# chariot_comms_b.net
KiCad netlist of a schematic drawn in EAGLE
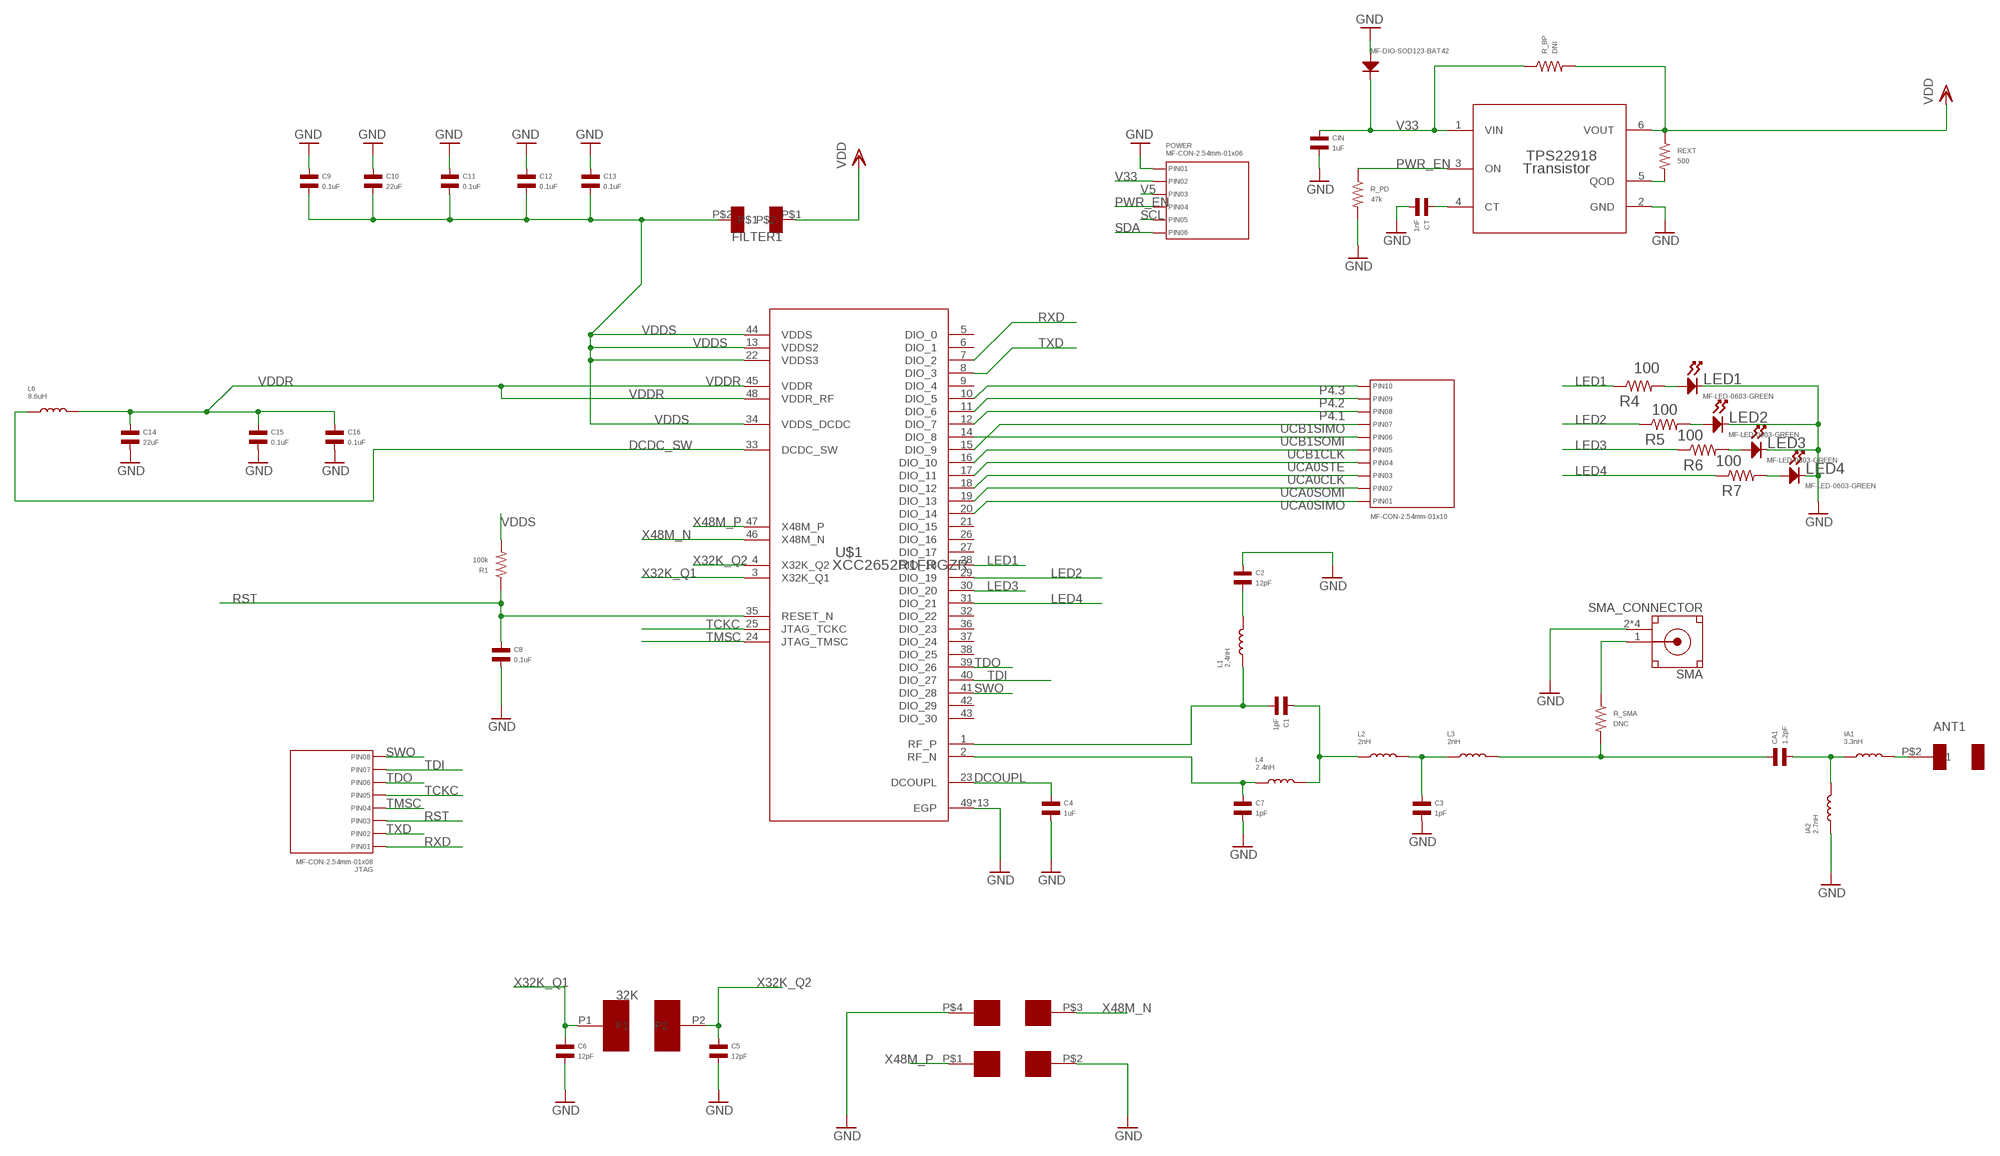
[diagram p0: schematic, sheet 1]

(export (version "E")
  (design (tool "Eeschema 10.0.6"))
  (components
    (comp (ref "32K")
      (value "FC-135")
      (footprint "eagle-import:FC-135")
      (libsource (lib "eagle-import") (part "FC-135"))
    )
    (comp (ref "48M")
      (value "NX2016SA-48M-EXS00A-CS05517")
      (footprint "eagle-import:NX2016SA-48M-EXS00A-CS05517")
      (libsource (lib "eagle-import") (part "NX2016SA-48M-EXS00A-CS05517"))
    )
    (comp (ref "ANT1")
      (value "2450AT18B100E")
      (footprint "eagle-import:2450AT18B100E")
      (libsource (lib "eagle-import") (part "2450AT18B100E"))
    )
    (comp (ref "C1")
      (value "1pF")
      (footprint "eagle-import:C0603")
      (libsource (lib "eagle-import") (part "CAPACITOR_NP_0603"))
    )
    (comp (ref "C2")
      (value "12pF")
      (footprint "eagle-import:C0603")
      (libsource (lib "eagle-import") (part "CAPACITOR_NP_0603"))
    )
    (comp (ref "C3")
      (value "1pF")
      (footprint "eagle-import:C0603")
      (libsource (lib "eagle-import") (part "CAPACITOR_NP_0603"))
    )
    (comp (ref "C4")
      (value "1uF")
      (footprint "eagle-import:C0603")
      (libsource (lib "eagle-import") (part "CAPACITOR_NP_0603"))
    )
    (comp (ref "C5")
      (value "12pF")
      (footprint "eagle-import:C0603")
      (libsource (lib "eagle-import") (part "CAPACITOR_NP_0603"))
    )
    (comp (ref "C6")
      (value "12pF")
      (footprint "eagle-import:C0603")
      (libsource (lib "eagle-import") (part "CAPACITOR_NP_0603"))
    )
    (comp (ref "C7")
      (value "1pF")
      (footprint "eagle-import:C0603")
      (libsource (lib "eagle-import") (part "CAPACITOR_NP_0603"))
    )
    (comp (ref "C8")
      (value "0.1uF")
      (footprint "eagle-import:C0603")
      (libsource (lib "eagle-import") (part "CAPACITOR_NP_0603"))
    )
    (comp (ref "C9")
      (value "0.1uF")
      (footprint "eagle-import:C0603")
      (libsource (lib "eagle-import") (part "CAPACITOR_NP_0603"))
    )
    (comp (ref "C10")
      (value "22uF")
      (footprint "eagle-import:C0603")
      (libsource (lib "eagle-import") (part "CAPACITOR_NP_0603"))
    )
    (comp (ref "C11")
      (value "0.1uF")
      (footprint "eagle-import:C0603")
      (libsource (lib "eagle-import") (part "CAPACITOR_NP_0603"))
    )
    (comp (ref "C12")
      (value "0.1uF")
      (footprint "eagle-import:C0603")
      (libsource (lib "eagle-import") (part "CAPACITOR_NP_0603"))
    )
    (comp (ref "C13")
      (value "0.1uF")
      (footprint "eagle-import:C0603")
      (libsource (lib "eagle-import") (part "CAPACITOR_NP_0603"))
    )
    (comp (ref "C14")
      (value "22uF")
      (footprint "eagle-import:C0603")
      (libsource (lib "eagle-import") (part "CAPACITOR_NP_0603"))
    )
    (comp (ref "C15")
      (value "0.1uF")
      (footprint "eagle-import:C0603")
      (libsource (lib "eagle-import") (part "CAPACITOR_NP_0603"))
    )
    (comp (ref "C16")
      (value "0.1uF")
      (footprint "eagle-import:C0603")
      (libsource (lib "eagle-import") (part "CAPACITOR_NP_0603"))
    )
    (comp (ref "CA1")
      (value "1.2pF")
      (footprint "eagle-import:C0603")
      (libsource (lib "eagle-import") (part "CAPACITOR_NP_0603"))
    )
    (comp (ref "CIN")
      (value "1uF")
      (footprint "eagle-import:C0603")
      (libsource (lib "eagle-import") (part "CAPACITOR_NP_0603"))
    )
    (comp (ref "COMMS_J")
      (value "MF-CON-2.54mm-01x10")
      (footprint "eagle-import:PTH_2.54MM_01X10")
      (fields (field (name "HOUSEPART") "YES"))
      (libsource (lib "eagle-import") (part "CON_01X10_PTH_2.54MM"))
    )
    (comp (ref "CT")
      (value "1nF")
      (footprint "eagle-import:C0603")
      (libsource (lib "eagle-import") (part "CAPACITOR_NP_0603"))
    )
    (comp (ref "D1")
      (value "MF-DIO-SOD123-BAT42")
      (footprint "eagle-import:SOD-123")
      (fields (field (name "HOUSEPART") "YES"))
      (libsource (lib "eagle-import") (part "DIODES_SOD-123_BAT42"))
    )
    (comp (ref "FILTER1")
      (value "BLM18HE152SN1D")
      (footprint "eagle-import:BLM18HE152SN1D")
      (libsource (lib "eagle-import") (part "BLM18HE152SN1D"))
    )
    (comp (ref "IA1")
      (value "3.3nH")
      (footprint "eagle-import:L0603")
      (libsource (lib "eagle-import") (part "INDUCTOR_0603"))
    )
    (comp (ref "IA2")
      (value "2.7nH")
      (footprint "eagle-import:L0603")
      (libsource (lib "eagle-import") (part "INDUCTOR_0603"))
    )
    (comp (ref "JTAG")
      (value "MF-CON-2.54mm-01x08")
      (footprint "eagle-import:PTH_2.54MM_01X08")
      (fields (field (name "HOUSEPART") "YES"))
      (libsource (lib "eagle-import") (part "CON_01X08_PTH_2.54MM"))
    )
    (comp (ref "L1")
      (value "2.4nH")
      (footprint "eagle-import:L0603")
      (libsource (lib "eagle-import") (part "INDUCTOR_0603"))
    )
    (comp (ref "L2")
      (value "2nH")
      (footprint "eagle-import:L0603")
      (libsource (lib "eagle-import") (part "INDUCTOR_0603"))
    )
    (comp (ref "L3")
      (value "2nH")
      (footprint "eagle-import:L0603")
      (libsource (lib "eagle-import") (part "INDUCTOR_0603"))
    )
    (comp (ref "L4")
      (value "2.4nH")
      (footprint "eagle-import:L0603")
      (libsource (lib "eagle-import") (part "INDUCTOR_0603"))
    )
    (comp (ref "L6")
      (value "8.6uH")
      (footprint "eagle-import:L0603")
      (libsource (lib "eagle-import") (part "INDUCTOR_0603"))
    )
    (comp (ref "LED1")
      (value "MF-LED-0603-GREEN")
      (footprint "eagle-import:LED0603")
      (fields (field (name "HOUSEPART") "YES"))
      (libsource (lib "eagle-import") (part "LED_SINGLE-0603-GREEN"))
    )
    (comp (ref "LED2")
      (value "MF-LED-0603-GREEN")
      (footprint "eagle-import:LED0603")
      (fields (field (name "HOUSEPART") "YES"))
      (libsource (lib "eagle-import") (part "LED_SINGLE-0603-GREEN"))
    )
    (comp (ref "LED3")
      (value "MF-LED-0603-GREEN")
      (footprint "eagle-import:LED0603")
      (fields (field (name "HOUSEPART") "YES"))
      (libsource (lib "eagle-import") (part "LED_SINGLE-0603-GREEN"))
    )
    (comp (ref "LED4")
      (value "MF-LED-0603-GREEN")
      (footprint "eagle-import:LED0603")
      (fields (field (name "HOUSEPART") "YES"))
      (libsource (lib "eagle-import") (part "LED_SINGLE-0603-GREEN"))
    )
    (comp (ref "POWER")
      (value "MF-CON-2.54mm-01x06")
      (footprint "eagle-import:PTH_2.54MM_01X06")
      (fields (field (name "HOUSEPART") "YES"))
      (libsource (lib "eagle-import") (part "CON_01X06_PTH_2.54MM"))
    )
    (comp (ref "R1")
      (value "100k")
      (footprint "eagle-import:R0603")
      (libsource (lib "eagle-import") (part "RESISTOR_0603"))
    )
    (comp (ref "R4")
      (value "100")
      (footprint "eagle-import:R0603")
      (libsource (lib "eagle-import") (part "RESISTOR_0603"))
    )
    (comp (ref "R5")
      (value "100")
      (footprint "eagle-import:R0603")
      (libsource (lib "eagle-import") (part "RESISTOR_0603"))
    )
    (comp (ref "R6")
      (value "100")
      (footprint "eagle-import:R0603")
      (libsource (lib "eagle-import") (part "RESISTOR_0603"))
    )
    (comp (ref "R7")
      (value "100")
      (footprint "eagle-import:R0603")
      (libsource (lib "eagle-import") (part "RESISTOR_0603"))
    )
    (comp (ref "REXT")
      (value "500")
      (footprint "eagle-import:R0603")
      (libsource (lib "eagle-import") (part "RESISTOR_0603"))
    )
    (comp (ref "R_BP")
      (value "DNI")
      (footprint "eagle-import:R0603")
      (libsource (lib "eagle-import") (part "RESISTOR_0603"))
    )
    (comp (ref "R_PD")
      (value "47k")
      (footprint "eagle-import:R0603")
      (libsource (lib "eagle-import") (part "RESISTOR_0603"))
    )
    (comp (ref "R_SMA")
      (value "DNC")
      (footprint "eagle-import:R0603")
      (libsource (lib "eagle-import") (part "RESISTOR_0603"))
    )
    (comp (ref "SMA")
      (value "SMA_CONNECTOR")
      (footprint "eagle-import:LPRS_SMA_CONNECTOR")
      (fields (field (name "MF") "LPRS") (field (name "MP") "SMA CONNECTOR"))
      (libsource (lib "eagle-import") (part "SMA_CONNECTOR"))
    )
    (comp (ref "TPS22918")
      (value "Transistor")
      (footprint "eagle-import:DBV0006A_N")
      (fields (field (name "MANUFACTURER") "Texas Instruments") (field (name "PARTNUMBER") "TPS22918TDBVRQ1"))
      (libsource (lib "eagle-import") (part "TPS22918TDBVRQ1"))
    )
    (comp (ref "U$1")
      (value "XCC2652R1FRGZR")
      (footprint "eagle-import:RGZ0048A")
      (libsource (lib "eagle-import") (part "XCC2652R1FRGZR"))
    )
  )
  (nets
    (net (code "1") (name "/DCDC_SW") (class "Default")
      (node (ref "L6") (pin "P$1") (pinfunction "P$1_P$1") (pintype "passive"))
      (node (ref "U$1") (pin "33") (pinfunction "DCDC_SW_33") (pintype "power_in"))
    )
    (net (code "2") (name "/DCOUPL") (class "Default")
      (node (ref "C4") (pin "P$1") (pinfunction "P$1_P$1") (pintype "passive"))
      (node (ref "U$1") (pin "23") (pinfunction "DCOUPL_23") (pintype "power_in"))
    )
    (net (code "3") (name "/LED1") (class "Default")
      (node (ref "R4") (pin "P$1") (pinfunction "P$1_P$1") (pintype "passive"))
      (node (ref "U$1") (pin "28") (pinfunction "DIO_18_28") (pintype "bidirectional"))
    )
    (net (code "4") (name "/LED2") (class "Default")
      (node (ref "R5") (pin "P$1") (pinfunction "P$1_P$1") (pintype "passive"))
      (node (ref "U$1") (pin "29") (pinfunction "DIO_19_29") (pintype "bidirectional"))
    )
    (net (code "5") (name "/LED3") (class "Default")
      (node (ref "R6") (pin "P$1") (pinfunction "P$1_P$1") (pintype "passive"))
      (node (ref "U$1") (pin "30") (pinfunction "DIO_20_30") (pintype "bidirectional"))
    )
    (net (code "6") (name "/LED4") (class "Default")
      (node (ref "R7") (pin "P$1") (pinfunction "P$1_P$1") (pintype "passive"))
      (node (ref "U$1") (pin "31") (pinfunction "DIO_21_31") (pintype "bidirectional"))
    )
    (net (code "7") (name "/P4.1") (class "Default")
      (node (ref "COMMS_J") (pin "P$8") (pinfunction "PIN8_P$8") (pintype "bidirectional"))
      (node (ref "U$1") (pin "12") (pinfunction "DIO_7_12") (pintype "bidirectional"))
    )
    (net (code "8") (name "/P4.2") (class "Default")
      (node (ref "COMMS_J") (pin "P$9") (pinfunction "PIN9_P$9") (pintype "bidirectional"))
      (node (ref "U$1") (pin "11") (pinfunction "DIO_6_11") (pintype "bidirectional"))
    )
    (net (code "9") (name "/P4.3") (class "Default")
      (node (ref "COMMS_J") (pin "P$10") (pinfunction "PIN10_P$10") (pintype "bidirectional"))
      (node (ref "U$1") (pin "10") (pinfunction "DIO_5_10") (pintype "bidirectional"))
    )
    (net (code "10") (name "/PWR_EN") (class "Default")
      (node (ref "POWER") (pin "P$4") (pinfunction "PIN4_P$4") (pintype "bidirectional"))
      (node (ref "R_PD") (pin "P$1") (pinfunction "P$1_P$1") (pintype "passive"))
      (node (ref "TPS22918") (pin "3") (pinfunction "ON_3") (pintype "input"))
    )
    (net (code "11") (name "/RST") (class "Default")
      (node (ref "C8") (pin "P$1") (pinfunction "P$1_P$1") (pintype "passive"))
      (node (ref "JTAG") (pin "P$3") (pinfunction "PIN3_P$3") (pintype "bidirectional"))
      (node (ref "R1") (pin "P$1") (pinfunction "P$1_P$1") (pintype "passive"))
      (node (ref "U$1") (pin "35") (pinfunction "RESET_N_35") (pintype "input"))
    )
    (net (code "12") (name "/RXD") (class "Default")
      (node (ref "JTAG") (pin "P$1") (pinfunction "PIN1_P$1") (pintype "bidirectional"))
      (node (ref "U$1") (pin "7") (pinfunction "DIO_2_7") (pintype "bidirectional"))
    )
    (net (code "13") (name "/SCL") (class "Default")
      (node (ref "POWER") (pin "P$5") (pinfunction "PIN5_P$5") (pintype "bidirectional"))
    )
    (net (code "14") (name "/SDA") (class "Default")
      (node (ref "POWER") (pin "P$6") (pinfunction "PIN6_P$6") (pintype "bidirectional"))
    )
    (net (code "15") (name "/SWO") (class "Default")
      (node (ref "JTAG") (pin "P$8") (pinfunction "PIN8_P$8") (pintype "bidirectional"))
      (node (ref "U$1") (pin "41") (pinfunction "DIO_28_41") (pintype "bidirectional"))
    )
    (net (code "16") (name "/TCKC") (class "Default")
      (node (ref "JTAG") (pin "P$5") (pinfunction "PIN5_P$5") (pintype "bidirectional"))
      (node (ref "U$1") (pin "25") (pinfunction "JTAG_TCKC_25") (pintype "bidirectional"))
    )
    (net (code "17") (name "/TDI") (class "Default")
      (node (ref "JTAG") (pin "P$7") (pinfunction "PIN7_P$7") (pintype "bidirectional"))
      (node (ref "U$1") (pin "40") (pinfunction "DIO_27_40") (pintype "bidirectional"))
    )
    (net (code "18") (name "/TDO") (class "Default")
      (node (ref "JTAG") (pin "P$6") (pinfunction "PIN6_P$6") (pintype "bidirectional"))
      (node (ref "U$1") (pin "39") (pinfunction "DIO_26_39") (pintype "bidirectional"))
    )
    (net (code "19") (name "/TMSC") (class "Default")
      (node (ref "JTAG") (pin "P$4") (pinfunction "PIN4_P$4") (pintype "bidirectional"))
      (node (ref "U$1") (pin "24") (pinfunction "JTAG_TMSC_24") (pintype "bidirectional"))
    )
    (net (code "20") (name "/TXD") (class "Default")
      (node (ref "JTAG") (pin "P$2") (pinfunction "PIN2_P$2") (pintype "bidirectional"))
      (node (ref "U$1") (pin "8") (pinfunction "DIO_3_8") (pintype "bidirectional"))
    )
    (net (code "21") (name "/UCA0CLK") (class "Default")
      (node (ref "COMMS_J") (pin "P$3") (pinfunction "PIN3_P$3") (pintype "bidirectional"))
      (node (ref "U$1") (pin "18") (pinfunction "DIO_12_18") (pintype "bidirectional"))
    )
    (net (code "22") (name "/UCA0SIMO") (class "Default")
      (node (ref "COMMS_J") (pin "P$1") (pinfunction "PIN1_P$1") (pintype "bidirectional"))
      (node (ref "U$1") (pin "20") (pinfunction "DIO_14_20") (pintype "bidirectional"))
    )
    (net (code "23") (name "/UCA0SOMI") (class "Default")
      (node (ref "COMMS_J") (pin "P$2") (pinfunction "PIN2_P$2") (pintype "bidirectional"))
      (node (ref "U$1") (pin "19") (pinfunction "DIO_13_19") (pintype "bidirectional"))
    )
    (net (code "24") (name "/UCA0STE") (class "Default")
      (node (ref "COMMS_J") (pin "P$4") (pinfunction "PIN4_P$4") (pintype "bidirectional"))
      (node (ref "U$1") (pin "17") (pinfunction "DIO_11_17") (pintype "bidirectional"))
    )
    (net (code "25") (name "/UCB1CLK") (class "Default")
      (node (ref "COMMS_J") (pin "P$5") (pinfunction "PIN5_P$5") (pintype "bidirectional"))
      (node (ref "U$1") (pin "16") (pinfunction "DIO_10_16") (pintype "bidirectional"))
    )
    (net (code "26") (name "/UCB1SIMO") (class "Default")
      (node (ref "COMMS_J") (pin "P$7") (pinfunction "PIN7_P$7") (pintype "bidirectional"))
      (node (ref "U$1") (pin "15") (pinfunction "DIO_9_15") (pintype "bidirectional"))
    )
    (net (code "27") (name "/UCB1SOMI") (class "Default")
      (node (ref "COMMS_J") (pin "P$6") (pinfunction "PIN6_P$6") (pintype "bidirectional"))
      (node (ref "U$1") (pin "14") (pinfunction "DIO_8_14") (pintype "bidirectional"))
    )
    (net (code "28") (name "/V5") (class "Default")
      (node (ref "POWER") (pin "P$3") (pinfunction "PIN3_P$3") (pintype "bidirectional"))
    )
    (net (code "29") (name "/V33") (class "Default")
      (node (ref "CIN") (pin "P$1") (pinfunction "P$1_P$1") (pintype "passive"))
      (node (ref "D1") (pin "CATHODE") (pinfunction "CATHODE_CATHODE") (pintype "bidirectional"))
      (node (ref "POWER") (pin "P$2") (pinfunction "PIN2_P$2") (pintype "bidirectional"))
      (node (ref "R_BP") (pin "P$1") (pinfunction "P$1_P$1") (pintype "passive"))
      (node (ref "TPS22918") (pin "1") (pinfunction "VIN_1") (pintype "power_in"))
    )
    (net (code "30") (name "/VDDR") (class "Default")
      (node (ref "C14") (pin "P$1") (pinfunction "P$1_P$1") (pintype "passive"))
      (node (ref "C15") (pin "P$1") (pinfunction "P$1_P$1") (pintype "passive"))
      (node (ref "C16") (pin "P$1") (pinfunction "P$1_P$1") (pintype "passive"))
      (node (ref "L6") (pin "P$2") (pinfunction "P$2_P$2") (pintype "passive"))
      (node (ref "U$1") (pin "45") (pinfunction "VDDR_45") (pintype "power_in"))
      (node (ref "U$1") (pin "48") (pinfunction "VDDR_RF_48") (pintype "power_in"))
    )
    (net (code "31") (name "/VDDS") (class "Default")
      (node (ref "C10") (pin "P$2") (pinfunction "P$2_P$2") (pintype "passive"))
      (node (ref "C11") (pin "P$2") (pinfunction "P$2_P$2") (pintype "passive"))
      (node (ref "C12") (pin "P$2") (pinfunction "P$2_P$2") (pintype "passive"))
      (node (ref "C13") (pin "P$2") (pinfunction "P$2_P$2") (pintype "passive"))
      (node (ref "C9") (pin "P$2") (pinfunction "P$2_P$2") (pintype "passive"))
      (node (ref "FILTER1") (pin "P$2") (pinfunction "P$2_P$2") (pintype "bidirectional"))
      (node (ref "R1") (pin "P$2") (pinfunction "P$2_P$2") (pintype "passive"))
      (node (ref "U$1") (pin "13") (pinfunction "VDDS2_13") (pintype "power_in"))
      (node (ref "U$1") (pin "22") (pinfunction "VDDS3_22") (pintype "power_in"))
      (node (ref "U$1") (pin "34") (pinfunction "VDDS_DCDC_34") (pintype "power_in"))
      (node (ref "U$1") (pin "44") (pinfunction "VDDS_44") (pintype "power_in"))
    )
    (net (code "32") (name "/X32K_Q1") (class "Default")
      (node (ref "32K") (pin "P1") (pinfunction "P1_P1") (pintype "bidirectional"))
      (node (ref "C6") (pin "P$1") (pinfunction "P$1_P$1") (pintype "passive"))
      (node (ref "U$1") (pin "3") (pinfunction "X32K_Q1_3") (pintype "bidirectional"))
    )
    (net (code "33") (name "/X32K_Q2") (class "Default")
      (node (ref "32K") (pin "P2") (pinfunction "P2_P2") (pintype "bidirectional"))
      (node (ref "C5") (pin "P$1") (pinfunction "P$1_P$1") (pintype "passive"))
      (node (ref "U$1") (pin "4") (pinfunction "X32K_Q2_4") (pintype "bidirectional"))
    )
    (net (code "34") (name "/X48M_N") (class "Default")
      (node (ref "48M") (pin "P$3") (pinfunction "P$3_P$3") (pintype "bidirectional"))
      (node (ref "U$1") (pin "46") (pinfunction "X48M_N_46") (pintype "bidirectional"))
    )
    (net (code "35") (name "/X48M_P") (class "Default")
      (node (ref "48M") (pin "P$1") (pinfunction "P$1_P$1") (pintype "bidirectional"))
      (node (ref "U$1") (pin "47") (pinfunction "X48M_P_47") (pintype "bidirectional"))
    )
    (net (code "36") (name "GND") (class "Default")
      (node (ref "48M") (pin "P$2") (pinfunction "P$2_P$2") (pintype "bidirectional"))
      (node (ref "48M") (pin "P$4") (pinfunction "P$4_P$4") (pintype "bidirectional"))
      (node (ref "C10") (pin "P$1") (pinfunction "P$1_P$1") (pintype "passive"))
      (node (ref "C11") (pin "P$1") (pinfunction "P$1_P$1") (pintype "passive"))
      (node (ref "C12") (pin "P$1") (pinfunction "P$1_P$1") (pintype "passive"))
      (node (ref "C13") (pin "P$1") (pinfunction "P$1_P$1") (pintype "passive"))
      (node (ref "C14") (pin "P$2") (pinfunction "P$2_P$2") (pintype "passive"))
      (node (ref "C15") (pin "P$2") (pinfunction "P$2_P$2") (pintype "passive"))
      (node (ref "C16") (pin "P$2") (pinfunction "P$2_P$2") (pintype "passive"))
      (node (ref "C2") (pin "P$1") (pinfunction "P$1_P$1") (pintype "passive"))
      (node (ref "C3") (pin "P$2") (pinfunction "P$2_P$2") (pintype "passive"))
      (node (ref "C4") (pin "P$2") (pinfunction "P$2_P$2") (pintype "passive"))
      (node (ref "C5") (pin "P$2") (pinfunction "P$2_P$2") (pintype "passive"))
      (node (ref "C6") (pin "P$2") (pinfunction "P$2_P$2") (pintype "passive"))
      (node (ref "C7") (pin "P$2") (pinfunction "P$2_P$2") (pintype "passive"))
      (node (ref "C8") (pin "P$2") (pinfunction "P$2_P$2") (pintype "passive"))
      (node (ref "C9") (pin "P$1") (pinfunction "P$1_P$1") (pintype "passive"))
      (node (ref "CIN") (pin "P$2") (pinfunction "P$2_P$2") (pintype "passive"))
      (node (ref "CT") (pin "P$2") (pinfunction "P$2_P$2") (pintype "passive"))
      (node (ref "D1") (pin "ANODE") (pinfunction "ANODE_ANODE") (pintype "bidirectional"))
      (node (ref "IA2") (pin "P$1") (pinfunction "P$1_P$1") (pintype "passive"))
      (node (ref "LED1") (pin "CATHODE") (pinfunction "CATHODE_CATHODE") (pintype "power_in"))
      (node (ref "LED2") (pin "CATHODE") (pinfunction "CATHODE_CATHODE") (pintype "power_in"))
      (node (ref "LED3") (pin "CATHODE") (pinfunction "CATHODE_CATHODE") (pintype "power_in"))
      (node (ref "LED4") (pin "CATHODE") (pinfunction "CATHODE_CATHODE") (pintype "power_in"))
      (node (ref "POWER") (pin "P$1") (pinfunction "PIN1_P$1") (pintype "bidirectional"))
      (node (ref "R_PD") (pin "P$2") (pinfunction "P$2_P$2") (pintype "passive"))
      (node (ref "SMA") (pin "2") (pinfunction "GND_2") (pintype "passive"))
      (node (ref "SMA") (pin "3") (pinfunction "GND_3") (pintype "passive"))
      (node (ref "SMA") (pin "4") (pinfunction "GND_4") (pintype "passive"))
      (node (ref "SMA") (pin "5") (pinfunction "GND_5") (pintype "passive"))
      (node (ref "TPS22918") (pin "2") (pinfunction "GND_2") (pintype "power_in"))
      (node (ref "U$1") (pin "49") (pinfunction "EGP_49") (pintype "power_in"))
      (node (ref "U$1") (pin "V1") (pinfunction "EGP_V1") (pintype "power_in"))
      (node (ref "U$1") (pin "V10") (pinfunction "EGP_V10") (pintype "power_in"))
      (node (ref "U$1") (pin "V11") (pinfunction "EGP_V11") (pintype "power_in"))
      (node (ref "U$1") (pin "V12") (pinfunction "EGP_V12") (pintype "power_in"))
      (node (ref "U$1") (pin "V2") (pinfunction "EGP_V2") (pintype "power_in"))
      (node (ref "U$1") (pin "V3") (pinfunction "EGP_V3") (pintype "power_in"))
      (node (ref "U$1") (pin "V4") (pinfunction "EGP_V4") (pintype "power_in"))
      (node (ref "U$1") (pin "V5") (pinfunction "EGP_V5") (pintype "power_in"))
      (node (ref "U$1") (pin "V6") (pinfunction "EGP_V6") (pintype "power_in"))
      (node (ref "U$1") (pin "V7") (pinfunction "EGP_V7") (pintype "power_in"))
      (node (ref "U$1") (pin "V8") (pinfunction "EGP_V8") (pintype "power_in"))
      (node (ref "U$1") (pin "V9") (pinfunction "EGP_V9") (pintype "power_in"))
    )
    (net (code "37") (name "Net-(ANT1-1)") (class "Default")
      (node (ref "ANT1") (pin "P$2") (pinfunction "1_P$2") (pintype "bidirectional"))
      (node (ref "IA1") (pin "P$2") (pinfunction "P$2_P$2") (pintype "passive"))
    )
    (net (code "38") (name "Net-(C1-PadP$1)") (class "Default")
      (node (ref "C1") (pin "P$1") (pinfunction "P$1_P$1") (pintype "passive"))
      (node (ref "L2") (pin "P$1") (pinfunction "P$1_P$1") (pintype "passive"))
      (node (ref "L4") (pin "P$2") (pinfunction "P$2_P$2") (pintype "passive"))
    )
    (net (code "39") (name "Net-(C2-PadP$2)") (class "Default")
      (node (ref "C2") (pin "P$2") (pinfunction "P$2_P$2") (pintype "passive"))
      (node (ref "L1") (pin "P$2") (pinfunction "P$2_P$2") (pintype "passive"))
    )
    (net (code "40") (name "Net-(C3-PadP$1)") (class "Default")
      (node (ref "C3") (pin "P$1") (pinfunction "P$1_P$1") (pintype "passive"))
      (node (ref "L2") (pin "P$2") (pinfunction "P$2_P$2") (pintype "passive"))
      (node (ref "L3") (pin "P$1") (pinfunction "P$1_P$1") (pintype "passive"))
    )
    (net (code "41") (name "Net-(CA1-PadP$1)") (class "Default")
      (node (ref "CA1") (pin "P$1") (pinfunction "P$1_P$1") (pintype "passive"))
      (node (ref "L3") (pin "P$2") (pinfunction "P$2_P$2") (pintype "passive"))
      (node (ref "R_SMA") (pin "P$2") (pinfunction "P$2_P$2") (pintype "passive"))
    )
    (net (code "42") (name "Net-(CA1-PadP$2)") (class "Default")
      (node (ref "CA1") (pin "P$2") (pinfunction "P$2_P$2") (pintype "passive"))
      (node (ref "IA1") (pin "P$1") (pinfunction "P$1_P$1") (pintype "passive"))
      (node (ref "IA2") (pin "P$2") (pinfunction "P$2_P$2") (pintype "passive"))
    )
    (net (code "43") (name "Net-(LED1-PadANODE)") (class "Default")
      (node (ref "LED1") (pin "ANODE") (pinfunction "ANODE_ANODE") (pintype "power_in"))
      (node (ref "R4") (pin "P$2") (pinfunction "P$2_P$2") (pintype "passive"))
    )
    (net (code "44") (name "Net-(LED2-PadANODE)") (class "Default")
      (node (ref "LED2") (pin "ANODE") (pinfunction "ANODE_ANODE") (pintype "power_in"))
      (node (ref "R5") (pin "P$2") (pinfunction "P$2_P$2") (pintype "passive"))
    )
    (net (code "45") (name "Net-(LED3-PadANODE)") (class "Default")
      (node (ref "LED3") (pin "ANODE") (pinfunction "ANODE_ANODE") (pintype "power_in"))
      (node (ref "R6") (pin "P$2") (pinfunction "P$2_P$2") (pintype "passive"))
    )
    (net (code "46") (name "Net-(LED4-PadANODE)") (class "Default")
      (node (ref "LED4") (pin "ANODE") (pinfunction "ANODE_ANODE") (pintype "power_in"))
      (node (ref "R7") (pin "P$2") (pinfunction "P$2_P$2") (pintype "passive"))
    )
    (net (code "47") (name "Net-(SMA-SIG)") (class "Default")
      (node (ref "R_SMA") (pin "P$1") (pinfunction "P$1_P$1") (pintype "passive"))
      (node (ref "SMA") (pin "1") (pinfunction "SIG_1") (pintype "passive"))
    )
    (net (code "48") (name "Net-(TPS22918-CT)") (class "Default")
      (node (ref "CT") (pin "P$1") (pinfunction "P$1_P$1") (pintype "passive"))
      (node (ref "TPS22918") (pin "4") (pinfunction "CT_4") (pintype "output"))
    )
    (net (code "49") (name "Net-(TPS22918-QOD)") (class "Default")
      (node (ref "REXT") (pin "P$2") (pinfunction "P$2_P$2") (pintype "passive"))
      (node (ref "TPS22918") (pin "5") (pinfunction "QOD_5") (pintype "input"))
    )
    (net (code "50") (name "Net-(U$1-RF_N)") (class "Default")
      (node (ref "C7") (pin "P$1") (pinfunction "P$1_P$1") (pintype "passive"))
      (node (ref "L4") (pin "P$1") (pinfunction "P$1_P$1") (pintype "passive"))
      (node (ref "U$1") (pin "2") (pinfunction "RF_N_2") (pintype "bidirectional"))
    )
    (net (code "51") (name "Net-(U$1-RF_P)") (class "Default")
      (node (ref "C1") (pin "P$2") (pinfunction "P$2_P$2") (pintype "passive"))
      (node (ref "L1") (pin "P$1") (pinfunction "P$1_P$1") (pintype "passive"))
      (node (ref "U$1") (pin "1") (pinfunction "RF_P_1") (pintype "bidirectional"))
    )
    (net (code "52") (name "VDD") (class "Default")
      (node (ref "FILTER1") (pin "P$1") (pinfunction "P$1_P$1") (pintype "bidirectional"))
      (node (ref "REXT") (pin "P$1") (pinfunction "P$1_P$1") (pintype "passive"))
      (node (ref "R_BP") (pin "P$2") (pinfunction "P$2_P$2") (pintype "passive"))
      (node (ref "TPS22918") (pin "6") (pinfunction "VOUT_6") (pintype "power_in"))
    )
    (net (code "53") (name "unconnected-(U$1-DIO_0-Pad5)") (class "Default")
      (node (ref "U$1") (pin "5") (pinfunction "DIO_0_5") (pintype "bidirectional"))
    )
    (net (code "54") (name "unconnected-(U$1-DIO_1-Pad6)") (class "Default")
      (node (ref "U$1") (pin "6") (pinfunction "DIO_1_6") (pintype "bidirectional"))
    )
    (net (code "55") (name "unconnected-(U$1-DIO_4-Pad9)") (class "Default")
      (node (ref "U$1") (pin "9") (pinfunction "DIO_4_9") (pintype "bidirectional"))
    )
    (net (code "56") (name "unconnected-(U$1-DIO_15-Pad21)") (class "Default")
      (node (ref "U$1") (pin "21") (pinfunction "DIO_15_21") (pintype "bidirectional"))
    )
    (net (code "57") (name "unconnected-(U$1-DIO_16-Pad26)") (class "Default")
      (node (ref "U$1") (pin "26") (pinfunction "DIO_16_26") (pintype "bidirectional"))
    )
    (net (code "58") (name "unconnected-(U$1-DIO_17-Pad27)") (class "Default")
      (node (ref "U$1") (pin "27") (pinfunction "DIO_17_27") (pintype "bidirectional"))
    )
    (net (code "59") (name "unconnected-(U$1-DIO_22-Pad32)") (class "Default")
      (node (ref "U$1") (pin "32") (pinfunction "DIO_22_32") (pintype "bidirectional"))
    )
    (net (code "60") (name "unconnected-(U$1-DIO_23-Pad36)") (class "Default")
      (node (ref "U$1") (pin "36") (pinfunction "DIO_23_36") (pintype "bidirectional"))
    )
    (net (code "61") (name "unconnected-(U$1-DIO_24-Pad37)") (class "Default")
      (node (ref "U$1") (pin "37") (pinfunction "DIO_24_37") (pintype "bidirectional"))
    )
    (net (code "62") (name "unconnected-(U$1-DIO_25-Pad38)") (class "Default")
      (node (ref "U$1") (pin "38") (pinfunction "DIO_25_38") (pintype "bidirectional"))
    )
    (net (code "63") (name "unconnected-(U$1-DIO_29-Pad42)") (class "Default")
      (node (ref "U$1") (pin "42") (pinfunction "DIO_29_42") (pintype "bidirectional"))
    )
    (net (code "64") (name "unconnected-(U$1-DIO_30-Pad43)") (class "Default")
      (node (ref "U$1") (pin "43") (pinfunction "DIO_30_43") (pintype "bidirectional"))
    )
  )
)
